# devkit.net
KiCad netlist of a schematic drawn in EAGLE
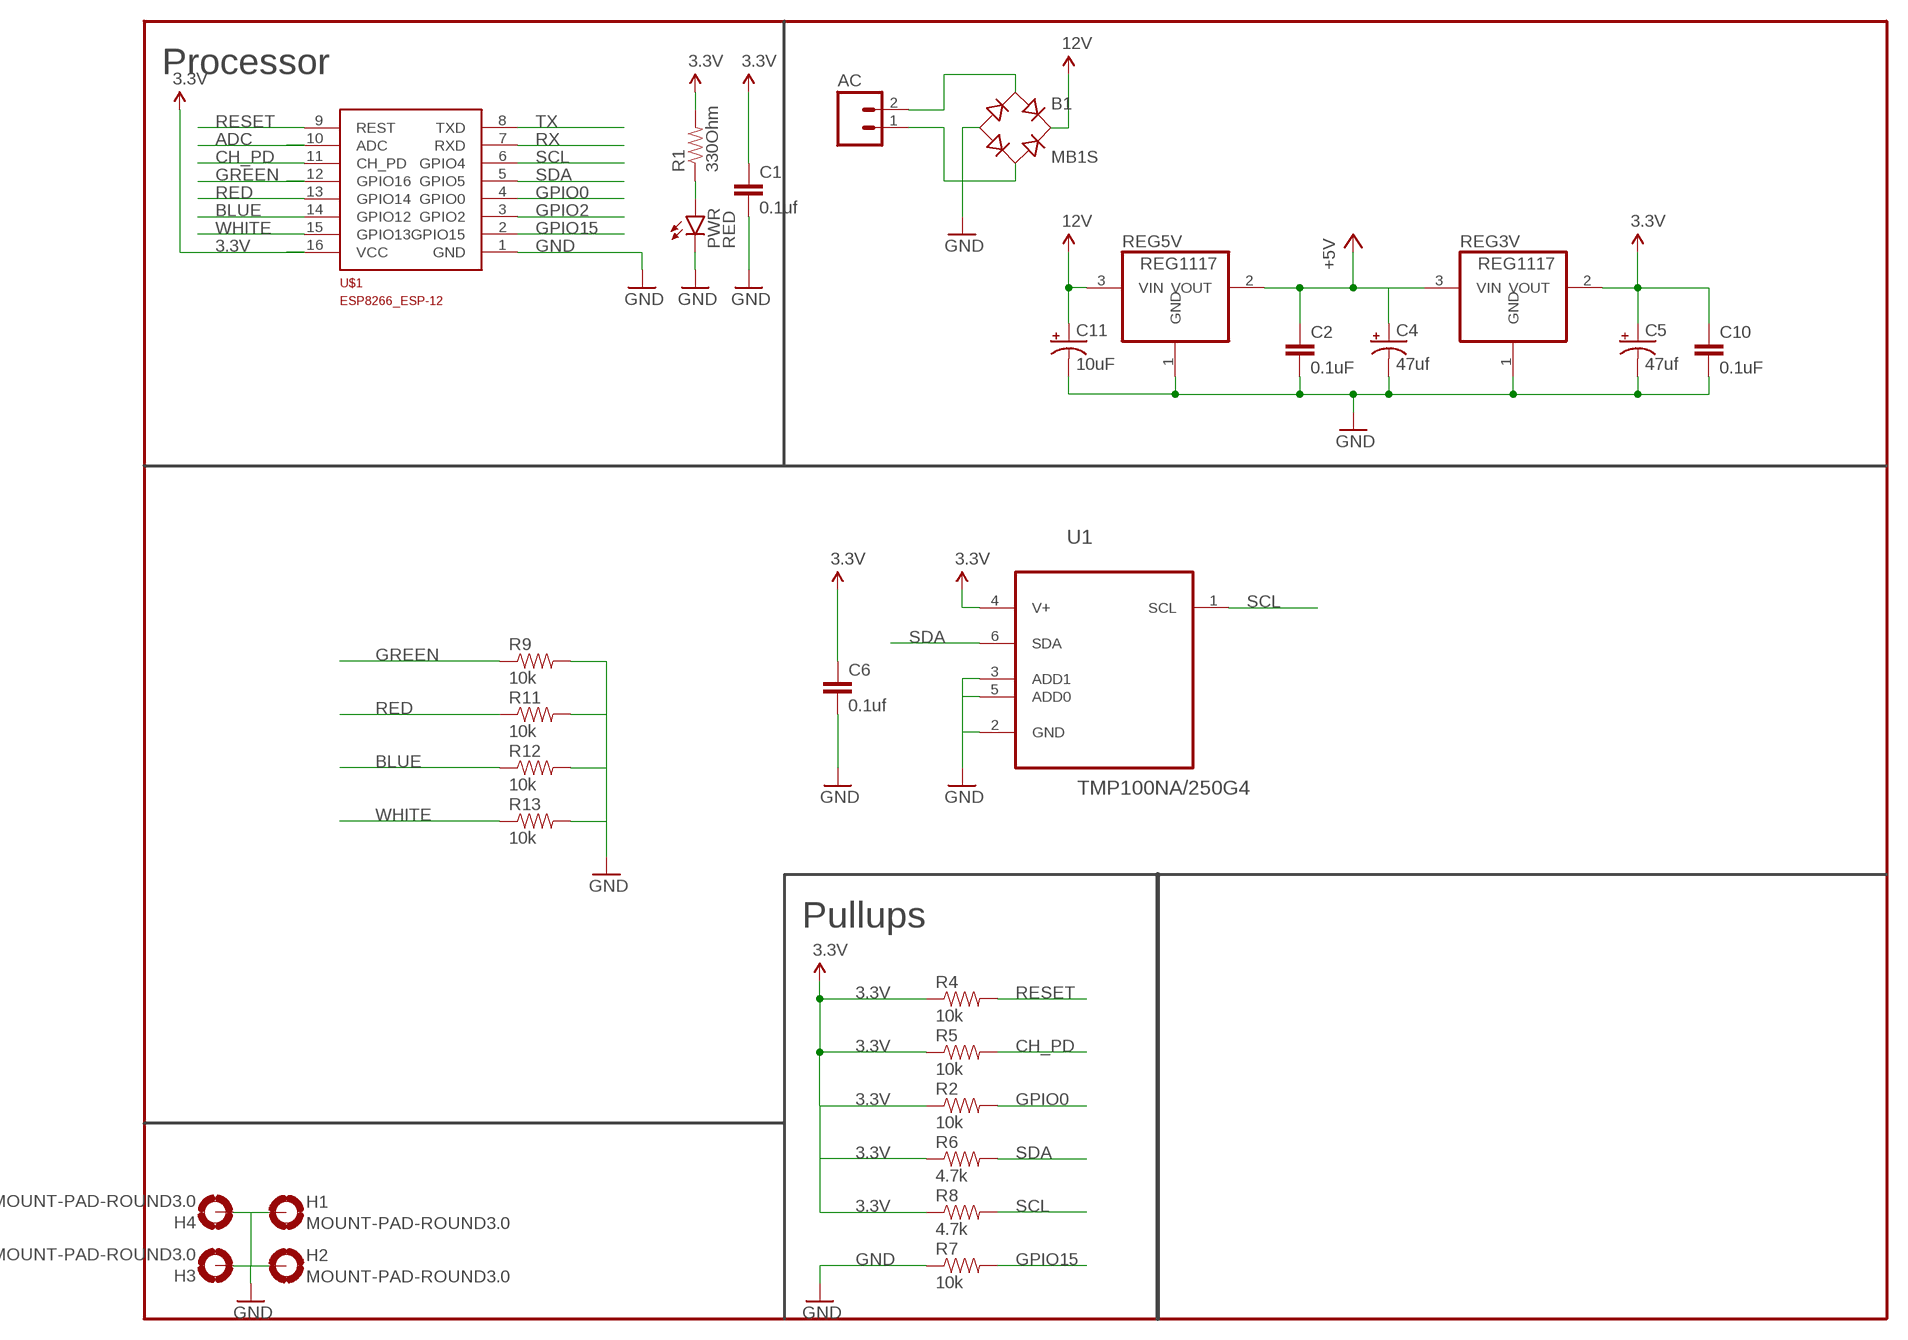
[diagram p0: schematic, sheet 1]
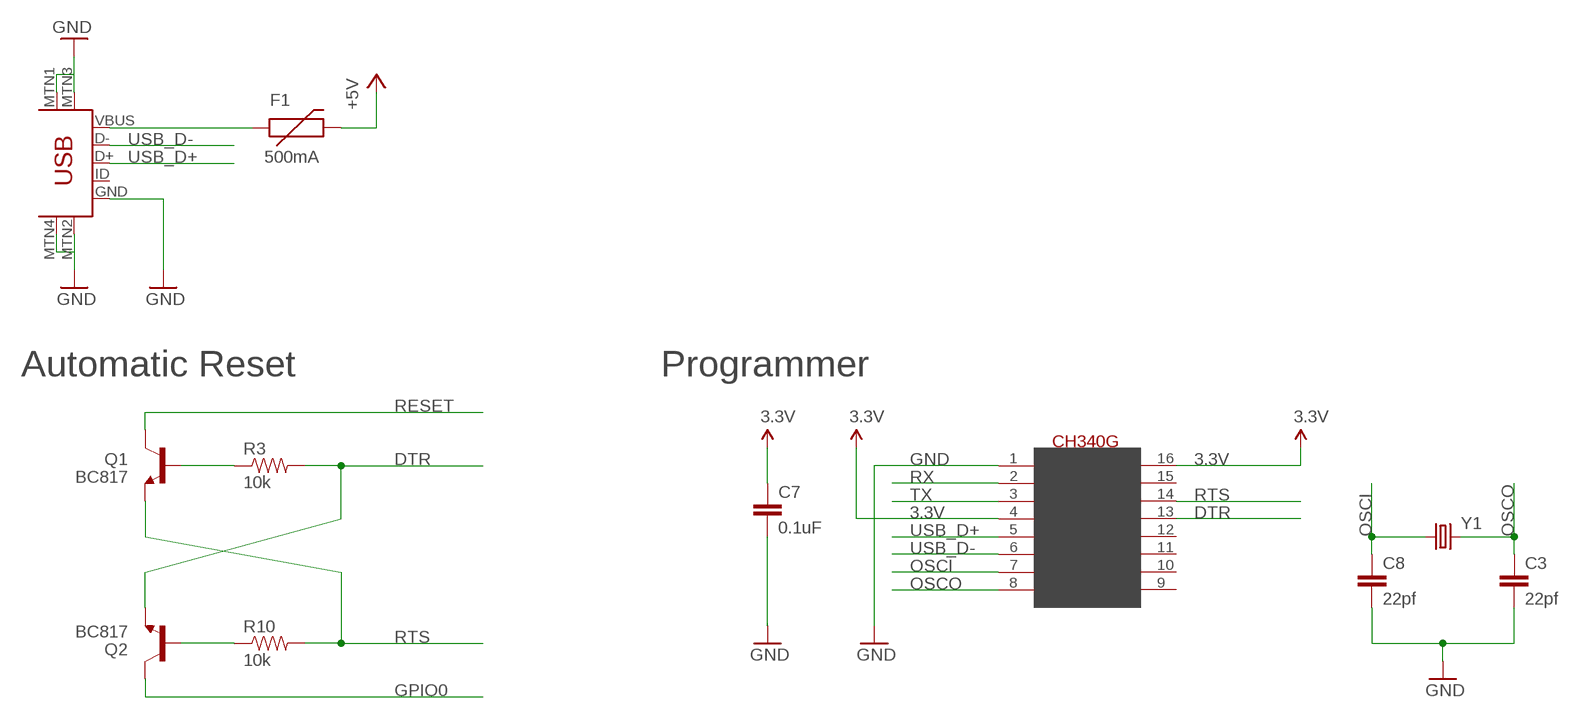
[diagram p1: schematic, sheet 2]
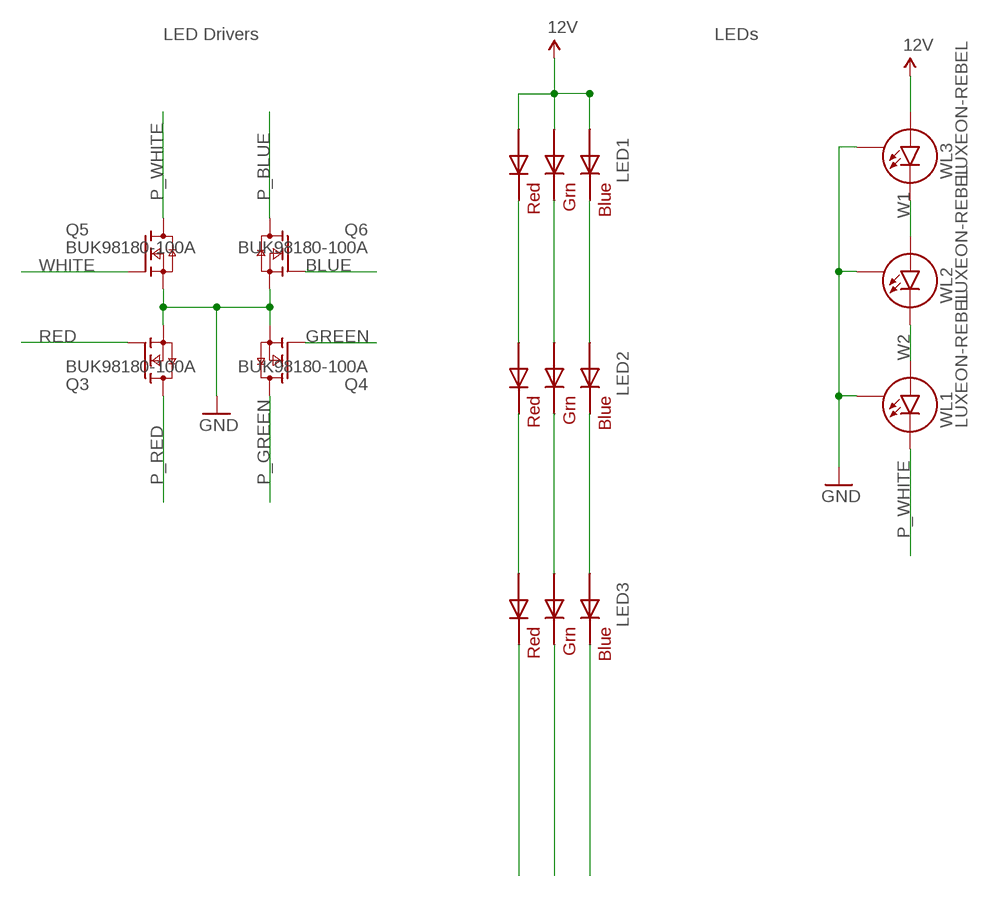
[diagram p2: schematic, sheet 3]

(export (version "E")
  (design (tool "Eeschema 10.0.6"))
  (components
    (comp (ref "C3")
      (value "22pf")
      (footprint "eagle-import:0805")
      (libsource (lib "eagle-import") (part "CAP0805"))
    )
    (comp (ref "C7")
      (value "0.1uF")
      (footprint "eagle-import:0805")
      (libsource (lib "eagle-import") (part "CAP0805"))
    )
    (comp (ref "C8")
      (value "22pf")
      (footprint "eagle-import:0805")
      (libsource (lib "eagle-import") (part "CAP0805"))
    )
    (comp (ref "F1")
      (value "500mA")
      (footprint "eagle-import:PTC-1206-WIDE")
      (libsource (lib "eagle-import") (part "PTCSMD-W"))
    )
    (comp (ref "Q1")
      (value "BC817")
      (footprint "eagle-import:SOT23-3")
      (libsource (lib "eagle-import") (part "TRANSISTOR_NPNSOT23-3"))
    )
    (comp (ref "Q2")
      (value "BC817")
      (footprint "eagle-import:SOT23-3")
      (libsource (lib "eagle-import") (part "TRANSISTOR_NPNSOT23-3"))
    )
    (comp (ref "R3")
      (value "10k")
      (footprint "eagle-import:0805")
      (libsource (lib "eagle-import") (part "RESISTOR0805-RES"))
    )
    (comp (ref "R10")
      (value "10k")
      (footprint "eagle-import:0805")
      (libsource (lib "eagle-import") (part "RESISTOR0805-RES"))
    )
    (comp (ref "U$2")
      (value "CH340G")
      (footprint "eagle-import:SOIC16")
      (libsource (lib "eagle-import") (part "CH340G"))
    )
    (comp (ref "U$3")
      (value "USB-MINIB-5PIN")
      (footprint "eagle-import:USB-MINIB")
      (libsource (lib "eagle-import") (part "USB-MINIB-5PIN"))
    )
    (comp (ref "Y1")
      (value "CRYSTALSMD")
      (footprint "eagle-import:HC49UP")
      (libsource (lib "eagle-import") (part "CRYSTALSMD"))
    )
    (comp (ref "AC")
      (value "M02JST-PTH-VERT")
      (footprint "eagle-import:JST-2-PTH-VERT")
      (libsource (lib "eagle-import") (part "M02JST-PTH-VERT"))
    )
    (comp (ref "B1")
      (value "MB1S")
      (footprint "eagle-import:SOIC-4")
      (libsource (lib "eagle-import") (part "MBS1"))
    )
    (comp (ref "C1")
      (value "0.1uf")
      (footprint "eagle-import:0805")
      (libsource (lib "eagle-import") (part "CAP0805"))
    )
    (comp (ref "C2")
      (value "0.1uF")
      (footprint "eagle-import:0805")
      (libsource (lib "eagle-import") (part "CAP0805"))
    )
    (comp (ref "C4")
      (value "47uf")
      (footprint "eagle-import:PANASONIC_C")
      (libsource (lib "eagle-import") (part "CAP_POLC"))
    )
    (comp (ref "C5")
      (value "47uf")
      (footprint "eagle-import:PANASONIC_C")
      (libsource (lib "eagle-import") (part "CAP_POLC"))
    )
    (comp (ref "C6")
      (value "0.1uf")
      (footprint "eagle-import:0805")
      (libsource (lib "eagle-import") (part "CAP0805"))
    )
    (comp (ref "C10")
      (value "0.1uF")
      (footprint "eagle-import:0805")
      (libsource (lib "eagle-import") (part "CAP0805"))
    )
    (comp (ref "C11")
      (value "10uF")
      (footprint "eagle-import:EIA3216")
      (libsource (lib "eagle-import") (part "10UF-TANT"))
    )
    (comp (ref "FRAME1")
      (value "FRAME-LETTERNO_PACKAGE")
      (footprint "eagle-import:DUMMY")
      (fields (field (name "DESIGNER") "Nobody"))
      (libsource (lib "eagle-import") (part "FRAME-LETTERNO_PACKAGE"))
    )
    (comp (ref "H1")
      (value "MOUNT-PAD-ROUND3.0")
      (footprint "eagle-import:3,0-PAD")
      (libsource (lib "eagle-import") (part "MOUNT-PAD-ROUND3.0"))
    )
    (comp (ref "H2")
      (value "MOUNT-PAD-ROUND3.0")
      (footprint "eagle-import:3,0-PAD")
      (libsource (lib "eagle-import") (part "MOUNT-PAD-ROUND3.0"))
    )
    (comp (ref "H3")
      (value "MOUNT-PAD-ROUND3.0")
      (footprint "eagle-import:3,0-PAD")
      (libsource (lib "eagle-import") (part "MOUNT-PAD-ROUND3.0"))
    )
    (comp (ref "H4")
      (value "MOUNT-PAD-ROUND3.0")
      (footprint "eagle-import:3,0-PAD")
      (libsource (lib "eagle-import") (part "MOUNT-PAD-ROUND3.0"))
    )
    (comp (ref "PWR")
      (value "RED")
      (footprint "eagle-import:LED-1206")
      (libsource (lib "eagle-import") (part "LED-RED1206"))
    )
    (comp (ref "R1")
      (value "330Ohm")
      (footprint "eagle-import:0805")
      (libsource (lib "eagle-import") (part "RESISTOR0805-RES"))
    )
    (comp (ref "R2")
      (value "10k")
      (footprint "eagle-import:0805")
      (libsource (lib "eagle-import") (part "RESISTOR0805-RES"))
    )
    (comp (ref "R4")
      (value "10k")
      (footprint "eagle-import:0805")
      (libsource (lib "eagle-import") (part "RESISTOR0805-RES"))
    )
    (comp (ref "R5")
      (value "10k")
      (footprint "eagle-import:0805")
      (libsource (lib "eagle-import") (part "RESISTOR0805-RES"))
    )
    (comp (ref "R6")
      (value "4.7k")
      (footprint "eagle-import:0805")
      (libsource (lib "eagle-import") (part "RESISTOR0805-RES"))
    )
    (comp (ref "R7")
      (value "10k")
      (footprint "eagle-import:0805")
      (libsource (lib "eagle-import") (part "RESISTOR0805-RES"))
    )
    (comp (ref "R8")
      (value "4.7k")
      (footprint "eagle-import:0805")
      (libsource (lib "eagle-import") (part "RESISTOR0805-RES"))
    )
    (comp (ref "R9")
      (value "10k")
      (footprint "eagle-import:0805")
      (libsource (lib "eagle-import") (part "RESISTOR0805-RES"))
    )
    (comp (ref "R11")
      (value "10k")
      (footprint "eagle-import:0805")
      (libsource (lib "eagle-import") (part "RESISTOR0805-RES"))
    )
    (comp (ref "R12")
      (value "10k")
      (footprint "eagle-import:0805")
      (libsource (lib "eagle-import") (part "RESISTOR0805-RES"))
    )
    (comp (ref "R13")
      (value "10k")
      (footprint "eagle-import:0805")
      (libsource (lib "eagle-import") (part "RESISTOR0805-RES"))
    )
    (comp (ref "REG3V")
      (value "REG1117")
      (footprint "eagle-import:SOT223")
      (libsource (lib "eagle-import") (part "REG1117"))
    )
    (comp (ref "REG5V")
      (value "REG1117")
      (footprint "eagle-import:SOT223")
      (libsource (lib "eagle-import") (part "REG1117"))
    )
    (comp (ref "U$1")
      (value "ESP8266_ESP-12")
      (footprint "eagle-import:ESP8266-ESP12")
      (libsource (lib "eagle-import") (part "ESP8266_ESP-12"))
    )
    (comp (ref "U1")
      (value "TMP100NA/250G4")
      (footprint "eagle-import:SOT95P280X145-6N")
      (libsource (lib "eagle-import") (part "TMP100NA/250G4"))
    )
    (comp (ref "LED1")
      (value "RGBLED5050")
      (footprint "eagle-import:RGBLED5050")
      (libsource (lib "eagle-import") (part "RGBLED5050"))
    )
    (comp (ref "LED2")
      (value "RGBLED5050")
      (footprint "eagle-import:RGBLED5050")
      (libsource (lib "eagle-import") (part "RGBLED5050"))
    )
    (comp (ref "LED3")
      (value "RGBLED5050")
      (footprint "eagle-import:RGBLED5050")
      (libsource (lib "eagle-import") (part "RGBLED5050"))
    )
    (comp (ref "Q3")
      (value "BUK98180-100A")
      (footprint "eagle-import:SOT223")
      (libsource (lib "eagle-import") (part "BUK98180-100A"))
    )
    (comp (ref "Q4")
      (value "BUK98180-100A")
      (footprint "eagle-import:SOT223")
      (libsource (lib "eagle-import") (part "BUK98180-100A"))
    )
    (comp (ref "Q5")
      (value "BUK98180-100A")
      (footprint "eagle-import:SOT223")
      (libsource (lib "eagle-import") (part "BUK98180-100A"))
    )
    (comp (ref "Q6")
      (value "BUK98180-100A")
      (footprint "eagle-import:SOT223")
      (libsource (lib "eagle-import") (part "BUK98180-100A"))
    )
    (comp (ref "WL1")
      (value "LUXEON-REBEL")
      (footprint "eagle-import:LUXEON-REBEL")
      (libsource (lib "eagle-import") (part "LUXEON-REBEL"))
    )
    (comp (ref "WL2")
      (value "LUXEON-REBEL")
      (footprint "eagle-import:LUXEON-REBEL")
      (libsource (lib "eagle-import") (part "LUXEON-REBEL"))
    )
    (comp (ref "WL3")
      (value "LUXEON-REBEL")
      (footprint "eagle-import:LUXEON-REBEL")
      (libsource (lib "eagle-import") (part "LUXEON-REBEL"))
    )
  )
  (nets
    (net (code "1") (name "+5V") (class "Default")
      (node (ref "C2") (pin "1") (pinfunction "1_1") (pintype "passive"))
      (node (ref "C4") (pin "+") (pinfunction "+_+") (pintype "passive"))
      (node (ref "F1") (pin "2") (pinfunction "2_2") (pintype "bidirectional"))
      (node (ref "REG3V") (pin "3") (pinfunction "VIN_3") (pintype "input"))
      (node (ref "REG5V") (pin "2") (pinfunction "VOUT_2") (pintype "output"))
    )
    (net (code "2") (name "3.3V") (class "Default")
      (node (ref "C1") (pin "1") (pinfunction "1_1") (pintype "passive"))
      (node (ref "C10") (pin "1") (pinfunction "1_1") (pintype "passive"))
      (node (ref "C5") (pin "+") (pinfunction "+_+") (pintype "passive"))
      (node (ref "C6") (pin "1") (pinfunction "1_1") (pintype "passive"))
      (node (ref "C7") (pin "1") (pinfunction "1_1") (pintype "passive"))
      (node (ref "R1") (pin "2") (pinfunction "2_2") (pintype "passive"))
      (node (ref "R2") (pin "1") (pinfunction "1_1") (pintype "passive"))
      (node (ref "R4") (pin "1") (pinfunction "1_1") (pintype "passive"))
      (node (ref "R5") (pin "1") (pinfunction "1_1") (pintype "passive"))
      (node (ref "R6") (pin "1") (pinfunction "1_1") (pintype "passive"))
      (node (ref "R8") (pin "1") (pinfunction "1_1") (pintype "passive"))
      (node (ref "REG3V") (pin "2") (pinfunction "VOUT_2") (pintype "output"))
      (node (ref "U$1") (pin "16") (pinfunction "VCC_16") (pintype "bidirectional"))
      (node (ref "U$2") (pin "16") (pinfunction "VCC_16") (pintype "bidirectional"))
      (node (ref "U$2") (pin "4") (pinfunction "V3_4") (pintype "bidirectional"))
      (node (ref "U1") (pin "4") (pinfunction "V+_4") (pintype "power_in"))
    )
    (net (code "3") (name "12V") (class "Default")
      (node (ref "B1") (pin "+") (pinfunction "+_+") (pintype "passive"))
      (node (ref "C11") (pin "A") (pinfunction "+_A") (pintype "passive"))
      (node (ref "LED1") (pin "1") (pinfunction "GREEN_A_1") (pintype "bidirectional"))
      (node (ref "LED1") (pin "2") (pinfunction "RED_A_2") (pintype "bidirectional"))
      (node (ref "LED1") (pin "3") (pinfunction "BLUE_A_3") (pintype "bidirectional"))
      (node (ref "REG5V") (pin "3") (pinfunction "VIN_3") (pintype "input"))
      (node (ref "WL3") (pin "ANODE") (pinfunction "A_ANODE") (pintype "passive"))
    )
    (net (code "4") (name "ADC") (class "Default")
      (node (ref "U$1") (pin "10") (pinfunction "ADC_10") (pintype "bidirectional"))
    )
    (net (code "5") (name "BLUE") (class "Default")
      (node (ref "Q6") (pin "1") (pinfunction "G_1") (pintype "passive"))
      (node (ref "R12") (pin "1") (pinfunction "1_1") (pintype "passive"))
      (node (ref "U$1") (pin "14") (pinfunction "GPIO12_14") (pintype "bidirectional"))
    )
    (net (code "6") (name "CH_PD") (class "Default")
      (node (ref "R5") (pin "2") (pinfunction "2_2") (pintype "passive"))
      (node (ref "U$1") (pin "11") (pinfunction "CH_PD_11") (pintype "bidirectional"))
    )
    (net (code "7") (name "DTR") (class "Default")
      (node (ref "Q2") (pin "2") (pinfunction "E_2") (pintype "passive"))
      (node (ref "R3") (pin "2") (pinfunction "2_2") (pintype "passive"))
      (node (ref "U$2") (pin "13") (pinfunction "DTR_13") (pintype "bidirectional"))
    )
    (net (code "8") (name "GND") (class "Default")
      (node (ref "B1") (pin "-") (pinfunction "-_-") (pintype "passive"))
      (node (ref "C1") (pin "2") (pinfunction "2_2") (pintype "passive"))
      (node (ref "C10") (pin "2") (pinfunction "2_2") (pintype "passive"))
      (node (ref "C11") (pin "C") (pinfunction "-_C") (pintype "passive"))
      (node (ref "C2") (pin "2") (pinfunction "2_2") (pintype "passive"))
      (node (ref "C3") (pin "2") (pinfunction "2_2") (pintype "passive"))
      (node (ref "C4") (pin "-") (pinfunction "-_-") (pintype "passive"))
      (node (ref "C5") (pin "-") (pinfunction "-_-") (pintype "passive"))
      (node (ref "C6") (pin "2") (pinfunction "2_2") (pintype "passive"))
      (node (ref "C7") (pin "2") (pinfunction "2_2") (pintype "passive"))
      (node (ref "C8") (pin "2") (pinfunction "2_2") (pintype "passive"))
      (node (ref "H1") (pin "B3,0") (pinfunction "MOUNT_B3,0") (pintype "passive"))
      (node (ref "H2") (pin "B3,0") (pinfunction "MOUNT_B3,0") (pintype "passive"))
      (node (ref "H3") (pin "B3,0") (pinfunction "MOUNT_B3,0") (pintype "passive"))
      (node (ref "H4") (pin "B3,0") (pinfunction "MOUNT_B3,0") (pintype "passive"))
      (node (ref "PWR") (pin "C") (pinfunction "C_C") (pintype "passive"))
      (node (ref "Q3") (pin "3") (pinfunction "S_3") (pintype "passive"))
      (node (ref "Q4") (pin "3") (pinfunction "S_3") (pintype "passive"))
      (node (ref "Q5") (pin "3") (pinfunction "S_3") (pintype "passive"))
      (node (ref "Q6") (pin "3") (pinfunction "S_3") (pintype "passive"))
      (node (ref "R11") (pin "2") (pinfunction "2_2") (pintype "passive"))
      (node (ref "R12") (pin "2") (pinfunction "2_2") (pintype "passive"))
      (node (ref "R13") (pin "2") (pinfunction "2_2") (pintype "passive"))
      (node (ref "R7") (pin "1") (pinfunction "1_1") (pintype "passive"))
      (node (ref "R9") (pin "2") (pinfunction "2_2") (pintype "passive"))
      (node (ref "REG3V") (pin "1") (pinfunction "GND_1") (pintype "power_in"))
      (node (ref "REG5V") (pin "1") (pinfunction "GND_1") (pintype "power_in"))
      (node (ref "U$1") (pin "1") (pinfunction "GND_1") (pintype "bidirectional"))
      (node (ref "U$2") (pin "1") (pinfunction "GND_1") (pintype "bidirectional"))
      (node (ref "U$3") (pin "GND") (pinfunction "GND_GND") (pintype "bidirectional"))
      (node (ref "U$3") (pin "MTN1") (pinfunction "MTN2_MTN1") (pintype "bidirectional"))
      (node (ref "U$3") (pin "MTN2") (pinfunction "MTN3_MTN2") (pintype "bidirectional"))
      (node (ref "U$3") (pin "MTN3") (pinfunction "MTN1_MTN3") (pintype "bidirectional"))
      (node (ref "U$3") (pin "MTN4") (pinfunction "MTN4_MTN4") (pintype "bidirectional"))
      (node (ref "U1") (pin "2") (pinfunction "GND_2") (pintype "passive"))
      (node (ref "U1") (pin "3") (pinfunction "ADD1_3") (pintype "input"))
      (node (ref "U1") (pin "5") (pinfunction "ADD0_5") (pintype "input"))
      (node (ref "WL1") (pin "P$3") (pinfunction "S_P$3") (pintype "bidirectional"))
      (node (ref "WL2") (pin "P$3") (pinfunction "S_P$3") (pintype "bidirectional"))
      (node (ref "WL3") (pin "P$3") (pinfunction "S_P$3") (pintype "bidirectional"))
    )
    (net (code "9") (name "GPIO0") (class "Default")
      (node (ref "Q2") (pin "3") (pinfunction "C_3") (pintype "passive"))
      (node (ref "R2") (pin "2") (pinfunction "2_2") (pintype "passive"))
      (node (ref "U$1") (pin "4") (pinfunction "GPIO0_4") (pintype "bidirectional"))
    )
    (net (code "10") (name "GPIO2") (class "Default")
      (node (ref "U$1") (pin "3") (pinfunction "GPIO2_3") (pintype "bidirectional"))
    )
    (net (code "11") (name "GPIO15") (class "Default")
      (node (ref "R7") (pin "2") (pinfunction "2_2") (pintype "passive"))
      (node (ref "U$1") (pin "2") (pinfunction "GPIO15_2") (pintype "bidirectional"))
    )
    (net (code "12") (name "GREEN") (class "Default")
      (node (ref "Q4") (pin "1") (pinfunction "G_1") (pintype "passive"))
      (node (ref "R9") (pin "1") (pinfunction "1_1") (pintype "passive"))
      (node (ref "U$1") (pin "12") (pinfunction "GPIO16_12") (pintype "bidirectional"))
    )
    (net (code "13") (name "Net-(B1-AC1)") (class "Default")
      (node (ref "AC") (pin "2") (pinfunction "2_2") (pintype "passive"))
      (node (ref "B1") (pin "~1") (pinfunction "AC1_~1") (pintype "passive"))
    )
    (net (code "14") (name "Net-(B1-AC2)") (class "Default")
      (node (ref "AC") (pin "1") (pinfunction "1_1") (pintype "passive"))
      (node (ref "B1") (pin "~2") (pinfunction "AC2_~2") (pintype "passive"))
    )
    (net (code "15") (name "Net-(F1-Pad1)") (class "Default")
      (node (ref "F1") (pin "1") (pinfunction "1_1") (pintype "bidirectional"))
      (node (ref "U$3") (pin "VBUS") (pinfunction "VBUS_VBUS") (pintype "bidirectional"))
    )
    (net (code "16") (name "Net-(LED1-BLUE_C)") (class "Default")
      (node (ref "LED1") (pin "4") (pinfunction "BLUE_C_4") (pintype "bidirectional"))
      (node (ref "LED2") (pin "3") (pinfunction "BLUE_A_3") (pintype "bidirectional"))
    )
    (net (code "17") (name "Net-(LED1-GREEN_C)") (class "Default")
      (node (ref "LED1") (pin "6") (pinfunction "GREEN_C_6") (pintype "bidirectional"))
      (node (ref "LED2") (pin "1") (pinfunction "GREEN_A_1") (pintype "bidirectional"))
    )
    (net (code "18") (name "Net-(LED1-RED_C)") (class "Default")
      (node (ref "LED1") (pin "5") (pinfunction "RED_C_5") (pintype "bidirectional"))
      (node (ref "LED2") (pin "2") (pinfunction "RED_A_2") (pintype "bidirectional"))
    )
    (net (code "19") (name "Net-(LED2-BLUE_C)") (class "Default")
      (node (ref "LED2") (pin "4") (pinfunction "BLUE_C_4") (pintype "bidirectional"))
      (node (ref "LED3") (pin "3") (pinfunction "BLUE_A_3") (pintype "bidirectional"))
    )
    (net (code "20") (name "Net-(LED2-GREEN_C)") (class "Default")
      (node (ref "LED2") (pin "6") (pinfunction "GREEN_C_6") (pintype "bidirectional"))
      (node (ref "LED3") (pin "1") (pinfunction "GREEN_A_1") (pintype "bidirectional"))
    )
    (net (code "21") (name "Net-(LED2-RED_C)") (class "Default")
      (node (ref "LED2") (pin "5") (pinfunction "RED_C_5") (pintype "bidirectional"))
      (node (ref "LED3") (pin "2") (pinfunction "RED_A_2") (pintype "bidirectional"))
    )
    (net (code "22") (name "Net-(PWR-PadA)") (class "Default")
      (node (ref "PWR") (pin "A") (pinfunction "A_A") (pintype "passive"))
      (node (ref "R1") (pin "1") (pinfunction "1_1") (pintype "passive"))
    )
    (net (code "23") (name "Net-(Q1-B)") (class "Default")
      (node (ref "Q1") (pin "1") (pinfunction "B_1") (pintype "passive"))
      (node (ref "R3") (pin "1") (pinfunction "1_1") (pintype "passive"))
    )
    (net (code "24") (name "Net-(Q2-B)") (class "Default")
      (node (ref "Q2") (pin "1") (pinfunction "B_1") (pintype "passive"))
      (node (ref "R10") (pin "1") (pinfunction "1_1") (pintype "passive"))
    )
    (net (code "25") (name "OSCI") (class "Default")
      (node (ref "C8") (pin "1") (pinfunction "1_1") (pintype "passive"))
      (node (ref "U$2") (pin "7") (pinfunction "XI_7") (pintype "bidirectional"))
      (node (ref "Y1") (pin "1") (pinfunction "1_1") (pintype "passive"))
    )
    (net (code "26") (name "OSCO") (class "Default")
      (node (ref "C3") (pin "1") (pinfunction "1_1") (pintype "passive"))
      (node (ref "U$2") (pin "8") (pinfunction "XO_8") (pintype "bidirectional"))
      (node (ref "Y1") (pin "2") (pinfunction "2_2") (pintype "passive"))
    )
    (net (code "27") (name "P_BLUE") (class "Default")
      (node (ref "LED3") (pin "4") (pinfunction "BLUE_C_4") (pintype "bidirectional"))
      (node (ref "Q6") (pin "2") (pinfunction "D_2") (pintype "passive"))
      (node (ref "Q6") (pin "4") (pinfunction "D_4") (pintype "passive"))
    )
    (net (code "28") (name "P_GREEN") (class "Default")
      (node (ref "LED3") (pin "6") (pinfunction "GREEN_C_6") (pintype "bidirectional"))
      (node (ref "Q4") (pin "2") (pinfunction "D_2") (pintype "passive"))
      (node (ref "Q4") (pin "4") (pinfunction "D_4") (pintype "passive"))
    )
    (net (code "29") (name "P_RED") (class "Default")
      (node (ref "LED3") (pin "5") (pinfunction "RED_C_5") (pintype "bidirectional"))
      (node (ref "Q3") (pin "2") (pinfunction "D_2") (pintype "passive"))
      (node (ref "Q3") (pin "4") (pinfunction "D_4") (pintype "passive"))
    )
    (net (code "30") (name "P_WHITE") (class "Default")
      (node (ref "Q5") (pin "2") (pinfunction "D_2") (pintype "passive"))
      (node (ref "Q5") (pin "4") (pinfunction "D_4") (pintype "passive"))
      (node (ref "WL1") (pin "CATHODE") (pinfunction "C_CATHODE") (pintype "passive"))
    )
    (net (code "31") (name "RED") (class "Default")
      (node (ref "Q3") (pin "1") (pinfunction "G_1") (pintype "passive"))
      (node (ref "R11") (pin "1") (pinfunction "1_1") (pintype "passive"))
      (node (ref "U$1") (pin "13") (pinfunction "GPIO14_13") (pintype "bidirectional"))
    )
    (net (code "32") (name "RESET") (class "Default")
      (node (ref "Q1") (pin "3") (pinfunction "C_3") (pintype "passive"))
      (node (ref "R4") (pin "2") (pinfunction "2_2") (pintype "passive"))
      (node (ref "U$1") (pin "9") (pinfunction "REST_9") (pintype "bidirectional"))
    )
    (net (code "33") (name "RTS") (class "Default")
      (node (ref "Q1") (pin "2") (pinfunction "E_2") (pintype "passive"))
      (node (ref "R10") (pin "2") (pinfunction "2_2") (pintype "passive"))
      (node (ref "U$2") (pin "14") (pinfunction "RTS_14") (pintype "bidirectional"))
    )
    (net (code "34") (name "RX") (class "Default")
      (node (ref "U$1") (pin "7") (pinfunction "RXD_7") (pintype "bidirectional"))
      (node (ref "U$2") (pin "2") (pinfunction "TX_2") (pintype "bidirectional"))
    )
    (net (code "35") (name "SCL") (class "Default")
      (node (ref "R8") (pin "2") (pinfunction "2_2") (pintype "passive"))
      (node (ref "U$1") (pin "6") (pinfunction "GPIO4_6") (pintype "bidirectional"))
      (node (ref "U1") (pin "1") (pinfunction "SCL_1") (pintype "output"))
    )
    (net (code "36") (name "SDA") (class "Default")
      (node (ref "R6") (pin "2") (pinfunction "2_2") (pintype "passive"))
      (node (ref "U$1") (pin "5") (pinfunction "GPIO5_5") (pintype "bidirectional"))
      (node (ref "U1") (pin "6") (pinfunction "SDA_6") (pintype "input"))
    )
    (net (code "37") (name "TX") (class "Default")
      (node (ref "U$1") (pin "8") (pinfunction "TXD_8") (pintype "bidirectional"))
      (node (ref "U$2") (pin "3") (pinfunction "RX_3") (pintype "bidirectional"))
    )
    (net (code "38") (name "USB_D+") (class "Default")
      (node (ref "U$2") (pin "5") (pinfunction "D+_5") (pintype "bidirectional"))
      (node (ref "U$3") (pin "D+") (pinfunction "D+_D+") (pintype "bidirectional"))
    )
    (net (code "39") (name "USB_D-") (class "Default")
      (node (ref "U$2") (pin "6") (pinfunction "D-_6") (pintype "bidirectional"))
      (node (ref "U$3") (pin "D-") (pinfunction "D-_D-") (pintype "bidirectional"))
    )
    (net (code "40") (name "W1") (class "Default")
      (node (ref "WL2") (pin "ANODE") (pinfunction "A_ANODE") (pintype "passive"))
      (node (ref "WL3") (pin "CATHODE") (pinfunction "C_CATHODE") (pintype "passive"))
    )
    (net (code "41") (name "W2") (class "Default")
      (node (ref "WL1") (pin "ANODE") (pinfunction "A_ANODE") (pintype "passive"))
      (node (ref "WL2") (pin "CATHODE") (pinfunction "C_CATHODE") (pintype "passive"))
    )
    (net (code "42") (name "WHITE") (class "Default")
      (node (ref "Q5") (pin "1") (pinfunction "G_1") (pintype "passive"))
      (node (ref "R13") (pin "1") (pinfunction "1_1") (pintype "passive"))
      (node (ref "U$1") (pin "15") (pinfunction "GPIO13_15") (pintype "bidirectional"))
    )
    (net (code "43") (name "unconnected-(U$2-CTS-Pad9)") (class "Default")
      (node (ref "U$2") (pin "9") (pinfunction "CTS_9") (pintype "bidirectional"))
    )
    (net (code "44") (name "unconnected-(U$2-DCD-Pad12)") (class "Default")
      (node (ref "U$2") (pin "12") (pinfunction "DCD_12") (pintype "bidirectional"))
    )
    (net (code "45") (name "unconnected-(U$2-DSR-Pad10)") (class "Default")
      (node (ref "U$2") (pin "10") (pinfunction "DSR_10") (pintype "bidirectional"))
    )
    (net (code "46") (name "unconnected-(U$2-RI-Pad11)") (class "Default")
      (node (ref "U$2") (pin "11") (pinfunction "RI_11") (pintype "bidirectional"))
    )
    (net (code "47") (name "unconnected-(U$2-RS232-Pad15)") (class "Default")
      (node (ref "U$2") (pin "15") (pinfunction "RS232_15") (pintype "bidirectional"))
    )
    (net (code "48") (name "unconnected-(U$3-PadID)") (class "Default")
      (node (ref "U$3") (pin "ID") (pinfunction "ID_ID") (pintype "bidirectional"))
    )
  )
)
